# pca63557_sheet3_motor.net
KiCad netlist of a schematic drawn in Altium Designer
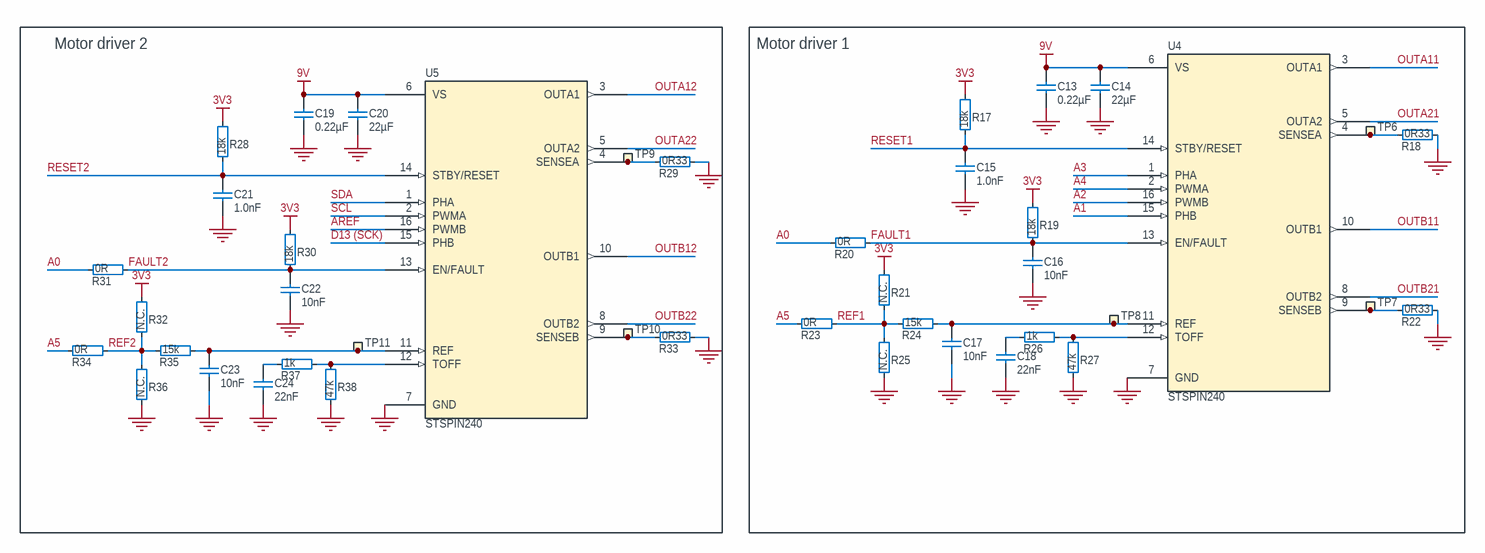
[diagram p0: pca63557_sheet3_motor.SchDoc]

(export (version "E")
  (design (tool "Eeschema 10.0.6"))
  (components
    (comp (ref "C13")
      (value "0.22µF")
      (footprint "CAPC1005X04L")
      (description "Capacitor, X7R, ±0.10%, 16V")
      (fields
        (field (name "PART NUMBER") "C0402-0.22µ-16V-X7R-CL05B224KO5NNNC")
        (field (name "MANUFACTURER") "Samsung Electro-Mechanics")
        (field (name "AUTHOR") "mam1")
      )
      (libsource (lib "AltiumLib") (part "CAP"))
    )
    (comp (ref "C14")
      (value "22µF")
      (footprint "CAPC1608X06L")
      (description "Capacitor, X5R, ±0.20%, 16V")
      (fields
        (field (name "PART NUMBER") "C0603-22µ-16V-X5R-CL10A226MO7JZNC")
        (field (name "MANUFACTURER") "Samsung Electro-Mechanics")
        (field (name "AUTHOR") "mam1")
      )
      (libsource (lib "AltiumLib") (part "CAP"))
    )
    (comp (ref "C15")
      (value "1.0nF")
      (footprint "CAPC1005X04L")
      (description "Capacitor, X7R, ±10%")
      (fields
        (field (name "PART NUMBER") "C0402-1n0")
        (field (name "MANUFACTURER") "N.A.")
        (field (name "AUTHOR") "rsk")
      )
      (libsource (lib "AltiumLib") (part "CAP"))
    )
    (comp (ref "C16")
      (value "10nF")
      (footprint "CAPC1005X04L")
      (description "Capacitor, X7R, ±10%")
      (fields
        (field (name "PART NUMBER") "C0402-10n")
        (field (name "MANUFACTURER") "N.A.")
        (field (name "AUTHOR") "rsk")
      )
      (libsource (lib "AltiumLib") (part "CAP"))
    )
    (comp (ref "C17")
      (value "10nF")
      (footprint "CAPC1005X04L")
      (description "Capacitor, X7R, ±10%")
      (fields
        (field (name "PART NUMBER") "C0402-10n")
        (field (name "MANUFACTURER") "N.A.")
        (field (name "AUTHOR") "rsk")
      )
      (libsource (lib "AltiumLib") (part "CAP"))
    )
    (comp (ref "C18")
      (value "22nF")
      (footprint "CAPC1005X04L")
      (description "Capacitor, X7R, ±10%")
      (fields
        (field (name "PART NUMBER") "C0402-22n")
        (field (name "MANUFACTURER") "N.A.")
        (field (name "AUTHOR") "rsk")
      )
      (libsource (lib "AltiumLib") (part "CAP"))
    )
    (comp (ref "C19")
      (value "0.22µF")
      (footprint "CAPC1005X04L")
      (description "Capacitor, X7R, ±0.10%, 16V")
      (fields
        (field (name "PART NUMBER") "C0402-0.22µ-16V-X7R-CL05B224KO5NNNC")
        (field (name "MANUFACTURER") "Samsung Electro-Mechanics")
        (field (name "AUTHOR") "mam1")
      )
      (libsource (lib "AltiumLib") (part "CAP"))
    )
    (comp (ref "C20")
      (value "22µF")
      (footprint "CAPC1608X06L")
      (description "Capacitor, X5R, ±0.20%, 16V")
      (fields
        (field (name "PART NUMBER") "C0603-22µ-16V-X5R-CL10A226MO7JZNC")
        (field (name "MANUFACTURER") "Samsung Electro-Mechanics")
        (field (name "AUTHOR") "mam1")
      )
      (libsource (lib "AltiumLib") (part "CAP"))
    )
    (comp (ref "C21")
      (value "1.0nF")
      (footprint "CAPC1005X04L")
      (description "Capacitor, X7R, ±10%")
      (fields
        (field (name "PART NUMBER") "C0402-1n0")
        (field (name "MANUFACTURER") "N.A.")
        (field (name "AUTHOR") "rsk")
      )
      (libsource (lib "AltiumLib") (part "CAP"))
    )
    (comp (ref "C22")
      (value "10nF")
      (footprint "CAPC1005X04L")
      (description "Capacitor, X7R, ±10%")
      (fields
        (field (name "PART NUMBER") "C0402-10n")
        (field (name "MANUFACTURER") "N.A.")
        (field (name "AUTHOR") "rsk")
      )
      (libsource (lib "AltiumLib") (part "CAP"))
    )
    (comp (ref "C23")
      (value "10nF")
      (footprint "CAPC1005X04L")
      (description "Capacitor, X7R, ±10%")
      (fields
        (field (name "PART NUMBER") "C0402-10n")
        (field (name "MANUFACTURER") "N.A.")
        (field (name "AUTHOR") "rsk")
      )
      (libsource (lib "AltiumLib") (part "CAP"))
    )
    (comp (ref "C24")
      (value "22nF")
      (footprint "CAPC1005X04L")
      (description "Capacitor, X7R, ±10%")
      (fields
        (field (name "PART NUMBER") "C0402-22n")
        (field (name "MANUFACTURER") "N.A.")
        (field (name "AUTHOR") "rsk")
      )
      (libsource (lib "AltiumLib") (part "CAP"))
    )
    (comp (ref "R17")
      (value "18k")
      (footprint "RESC1005X04L")
      (description "Resistor, ±1%, 0.063W")
      (fields
        (field (name "PART NUMBER") "R0402-18k")
        (field (name "MANUFACTURER") "N.A.")
        (field (name "AUTHOR") "rsk")
      )
      (libsource (lib "AltiumLib") (part "RES"))
    )
    (comp (ref "R18")
      (value "0R33")
      (footprint "RESC3216X08N")
      (description "330 Ohms ±0.5% 1W Chip Resistor 1206 (3216 Metric)")
      (fields
        (field (name "PART NUMBER") "R1206-0R33-0.5%-1W-HRG3216P-3300-D-T1")
        (field (name "MANUFACTURER") "Susumu")
        (field (name "AUTHOR") "mam1")
      )
      (libsource (lib "AltiumLib") (part "RES"))
    )
    (comp (ref "R19")
      (value "18k")
      (footprint "RESC1005X04L")
      (description "Resistor, ±1%, 0.063W")
      (fields
        (field (name "PART NUMBER") "R0402-18k")
        (field (name "MANUFACTURER") "N.A.")
        (field (name "AUTHOR") "rsk")
      )
      (libsource (lib "AltiumLib") (part "RES"))
    )
    (comp (ref "R20")
      (value "0R")
      (footprint "RESC1005X04L")
      (description "Resistor, ±5%, 0.063W")
      (fields
        (field (name "PART NUMBER") "R0402-0R")
        (field (name "MANUFACTURER") "N.A.")
        (field (name "AUTHOR") "rsk")
      )
      (libsource (lib "AltiumLib") (part "RES"))
    )
    (comp (ref "R21")
      (value "N.C.")
      (footprint "RESC1005X04L_NC")
      (description "Not mounted")
      (fields
        (field (name "PART NUMBER") "R0402-N.C.")
        (field (name "MANUFACTURER") "N.A.")
        (field (name "AUTHOR") "rsk")
      )
      (libsource (lib "AltiumLib") (part "RES"))
    )
    (comp (ref "R22")
      (value "0R33")
      (footprint "RESC3216X08N")
      (description "330 Ohms ±0.5% 1W Chip Resistor 1206 (3216 Metric)")
      (fields
        (field (name "PART NUMBER") "R1206-0R33-0.5%-1W-HRG3216P-3300-D-T1")
        (field (name "MANUFACTURER") "Susumu")
        (field (name "AUTHOR") "mam1")
      )
      (libsource (lib "AltiumLib") (part "RES"))
    )
    (comp (ref "R23")
      (value "0R")
      (footprint "RESC1005X04L")
      (description "Resistor, ±5%, 0.063W")
      (fields
        (field (name "PART NUMBER") "R0402-0R")
        (field (name "MANUFACTURER") "N.A.")
        (field (name "AUTHOR") "rsk")
      )
      (libsource (lib "AltiumLib") (part "RES"))
    )
    (comp (ref "R24")
      (value "15k")
      (footprint "RESC1005X04L")
      (description "Resistor, ±1%, 0.063W")
      (fields
        (field (name "PART NUMBER") "R0402-15k")
        (field (name "MANUFACTURER") "N.A.")
        (field (name "AUTHOR") "rsk")
      )
      (libsource (lib "AltiumLib") (part "RES"))
    )
    (comp (ref "R25")
      (value "N.C.")
      (footprint "RESC1005X04L_NC")
      (description "Not mounted")
      (fields
        (field (name "PART NUMBER") "R0402-N.C.")
        (field (name "MANUFACTURER") "N.A.")
        (field (name "AUTHOR") "rsk")
      )
      (libsource (lib "AltiumLib") (part "RES"))
    )
    (comp (ref "R26")
      (value "1k")
      (footprint "RESC1005X04L")
      (description "Resistor, ±1%, 0.063W")
      (fields
        (field (name "PART NUMBER") "R0402-1k0")
        (field (name "MANUFACTURER") "N.A.")
        (field (name "AUTHOR") "rsk")
      )
      (libsource (lib "AltiumLib") (part "RES"))
    )
    (comp (ref "R27")
      (value "47k")
      (footprint "RESC1005X04L")
      (description "Resistor, ±1%, 0.063W")
      (fields
        (field (name "PART NUMBER") "R0402-47k")
        (field (name "MANUFACTURER") "N.A.")
        (field (name "AUTHOR") "rsk")
      )
      (libsource (lib "AltiumLib") (part "RES"))
    )
    (comp (ref "R28")
      (value "18k")
      (footprint "RESC1005X04L")
      (description "Resistor, ±1%, 0.063W")
      (fields
        (field (name "PART NUMBER") "R0402-18k")
        (field (name "MANUFACTURER") "N.A.")
        (field (name "AUTHOR") "rsk")
      )
      (libsource (lib "AltiumLib") (part "RES"))
    )
    (comp (ref "R29")
      (value "0R33")
      (footprint "RESC3216X08N")
      (description "330 Ohms ±0.5% 1W Chip Resistor 1206 (3216 Metric)")
      (fields
        (field (name "PART NUMBER") "R1206-0R33-0.5%-1W-HRG3216P-3300-D-T1")
        (field (name "MANUFACTURER") "Susumu")
        (field (name "AUTHOR") "mam1")
      )
      (libsource (lib "AltiumLib") (part "RES"))
    )
    (comp (ref "R30")
      (value "18k")
      (footprint "RESC1005X04L")
      (description "Resistor, ±1%, 0.063W")
      (fields
        (field (name "PART NUMBER") "R0402-18k")
        (field (name "MANUFACTURER") "N.A.")
        (field (name "AUTHOR") "rsk")
      )
      (libsource (lib "AltiumLib") (part "RES"))
    )
    (comp (ref "R31")
      (value "0R")
      (footprint "RESC1005X04L")
      (description "Resistor, ±5%, 0.063W")
      (fields
        (field (name "PART NUMBER") "R0402-0R")
        (field (name "MANUFACTURER") "N.A.")
        (field (name "AUTHOR") "rsk")
      )
      (libsource (lib "AltiumLib") (part "RES"))
    )
    (comp (ref "R32")
      (value "N.C.")
      (footprint "RESC1005X04L_NC")
      (description "Not mounted")
      (fields
        (field (name "PART NUMBER") "R0402-N.C.")
        (field (name "MANUFACTURER") "N.A.")
        (field (name "AUTHOR") "rsk")
      )
      (libsource (lib "AltiumLib") (part "RES"))
    )
    (comp (ref "R33")
      (value "0R33")
      (footprint "RESC3216X08N")
      (description "330 Ohms ±0.5% 1W Chip Resistor 1206 (3216 Metric)")
      (fields
        (field (name "PART NUMBER") "R1206-0R33-0.5%-1W-HRG3216P-3300-D-T1")
        (field (name "MANUFACTURER") "Susumu")
        (field (name "AUTHOR") "mam1")
      )
      (libsource (lib "AltiumLib") (part "RES"))
    )
    (comp (ref "R34")
      (value "0R")
      (footprint "RESC1005X04L")
      (description "Resistor, ±5%, 0.063W")
      (fields
        (field (name "PART NUMBER") "R0402-0R")
        (field (name "MANUFACTURER") "N.A.")
        (field (name "AUTHOR") "rsk")
      )
      (libsource (lib "AltiumLib") (part "RES"))
    )
    (comp (ref "R35")
      (value "15k")
      (footprint "RESC1005X04L")
      (description "Resistor, ±1%, 0.063W")
      (fields
        (field (name "PART NUMBER") "R0402-15k")
        (field (name "MANUFACTURER") "N.A.")
        (field (name "AUTHOR") "rsk")
      )
      (libsource (lib "AltiumLib") (part "RES"))
    )
    (comp (ref "R36")
      (value "N.C.")
      (footprint "RESC1005X04L_NC")
      (description "Not mounted")
      (fields
        (field (name "PART NUMBER") "R0402-N.C.")
        (field (name "MANUFACTURER") "N.A.")
        (field (name "AUTHOR") "rsk")
      )
      (libsource (lib "AltiumLib") (part "RES"))
    )
    (comp (ref "R37")
      (value "1k")
      (footprint "RESC1005X04L")
      (description "Resistor, ±1%, 0.063W")
      (fields
        (field (name "PART NUMBER") "R0402-1k0")
        (field (name "MANUFACTURER") "N.A.")
        (field (name "AUTHOR") "rsk")
      )
      (libsource (lib "AltiumLib") (part "RES"))
    )
    (comp (ref "R38")
      (value "47k")
      (footprint "RESC1005X04L")
      (description "Resistor, ±1%, 0.063W")
      (fields
        (field (name "PART NUMBER") "R0402-47k")
        (field (name "MANUFACTURER") "N.A.")
        (field (name "AUTHOR") "rsk")
      )
      (libsource (lib "AltiumLib") (part "RES"))
    )
    (comp (ref "TP6")
      (value "Ø1.5mm,SMD")
      (footprint "TP_SMD_D1.5mm")
      (description "1.5mm circular SMD testpad")
      (fields
        (field (name "PART NUMBER") "TP_SMD_Ø1.5MM")
        (field (name "MANUFACTURER") "Nordic Semiconductor")
        (field (name "AUTHOR") "rsk")
      )
      (libsource (lib "AltiumLib") (part "TESTPAD"))
    )
    (comp (ref "TP7")
      (value "Ø1.5mm,SMD")
      (footprint "TP_SMD_D1.5mm")
      (description "1.5mm circular SMD testpad")
      (fields
        (field (name "PART NUMBER") "TP_SMD_Ø1.5MM")
        (field (name "MANUFACTURER") "Nordic Semiconductor")
        (field (name "AUTHOR") "rsk")
      )
      (libsource (lib "AltiumLib") (part "TESTPAD"))
    )
    (comp (ref "TP8")
      (value "Ø1.5mm,SMD")
      (footprint "TP_SMD_D1.5mm")
      (description "1.5mm circular SMD testpad")
      (fields
        (field (name "PART NUMBER") "TP_SMD_Ø1.5MM")
        (field (name "MANUFACTURER") "Nordic Semiconductor")
        (field (name "AUTHOR") "rsk")
      )
      (libsource (lib "AltiumLib") (part "TESTPAD"))
    )
    (comp (ref "TP9")
      (value "Ø1.5mm,SMD")
      (footprint "TP_SMD_D1.5mm")
      (description "1.5mm circular SMD testpad")
      (fields
        (field (name "PART NUMBER") "TP_SMD_Ø1.5MM")
        (field (name "MANUFACTURER") "Nordic Semiconductor")
        (field (name "AUTHOR") "rsk")
      )
      (libsource (lib "AltiumLib") (part "TESTPAD"))
    )
    (comp (ref "TP10")
      (value "Ø1.5mm,SMD")
      (footprint "TP_SMD_D1.5mm")
      (description "1.5mm circular SMD testpad")
      (fields
        (field (name "PART NUMBER") "TP_SMD_Ø1.5MM")
        (field (name "MANUFACTURER") "Nordic Semiconductor")
        (field (name "AUTHOR") "rsk")
      )
      (libsource (lib "AltiumLib") (part "TESTPAD"))
    )
    (comp (ref "TP11")
      (value "Ø1.5mm,SMD")
      (footprint "TP_SMD_D1.5mm")
      (description "1.5mm circular SMD testpad")
      (fields
        (field (name "PART NUMBER") "TP_SMD_Ø1.5MM")
        (field (name "MANUFACTURER") "Nordic Semiconductor")
        (field (name "AUTHOR") "rsk")
      )
      (libsource (lib "AltiumLib") (part "TESTPAD"))
    )
    (comp (ref "U4")
      (value "STSPIN240")
      (footprint "STSPIN240")
      (description "LOW VOLTAGE DUAL BRUSH DC MOTOR")
      (fields (field (name "MANUFACTURER") "STMicroelectronics") (field (name "AUTHOR") "mam1"))
      (libsource (lib "AltiumLib") (part "STSPIN240"))
    )
    (comp (ref "U5")
      (value "STSPIN240")
      (footprint "STSPIN240")
      (description "LOW VOLTAGE DUAL BRUSH DC MOTOR")
      (fields (field (name "MANUFACTURER") "STMicroelectronics") (field (name "AUTHOR") "mam1"))
      (libsource (lib "AltiumLib") (part "STSPIN240"))
    )
  )
  (nets
    (net (code "1") (name "/A0") (class "Default")
      (node (ref "R20") (pin "1") (pinfunction "1_1") (pintype "passive"))
      (node (ref "R31") (pin "1") (pinfunction "1_1") (pintype "passive"))
    )
    (net (code "2") (name "/A1") (class "Default")
      (node (ref "U4") (pin "15") (pinfunction "PHB_15") (pintype "input"))
    )
    (net (code "3") (name "/A2") (class "Default")
      (node (ref "U4") (pin "16") (pinfunction "PWMB_16") (pintype "input"))
    )
    (net (code "4") (name "/A3") (class "Default")
      (node (ref "U4") (pin "1") (pinfunction "PHA_1") (pintype "input"))
    )
    (net (code "5") (name "/A4") (class "Default")
      (node (ref "U4") (pin "2") (pinfunction "PWMA_2") (pintype "input"))
    )
    (net (code "6") (name "/A5") (class "Default")
      (node (ref "R23") (pin "1") (pinfunction "1_1") (pintype "passive"))
      (node (ref "R34") (pin "1") (pinfunction "1_1") (pintype "passive"))
    )
    (net (code "7") (name "/AREF") (class "Default")
      (node (ref "U5") (pin "16") (pinfunction "PWMB_16") (pintype "input"))
    )
    (net (code "8") (name "/D13 (SCK)") (class "Default")
      (node (ref "U5") (pin "15") (pinfunction "PHB_15") (pintype "input"))
    )
    (net (code "9") (name "/FAULT1") (class "Default")
      (node (ref "C16") (pin "2") (pinfunction "2_2") (pintype "passive"))
      (node (ref "R19") (pin "1") (pinfunction "1_1") (pintype "passive"))
      (node (ref "R20") (pin "2") (pinfunction "2_2") (pintype "passive"))
      (node (ref "U4") (pin "13") (pinfunction "EN/FAULT_13") (pintype "input"))
    )
    (net (code "10") (name "/FAULT2") (class "Default")
      (node (ref "C22") (pin "2") (pinfunction "2_2") (pintype "passive"))
      (node (ref "R30") (pin "1") (pinfunction "1_1") (pintype "passive"))
      (node (ref "R31") (pin "2") (pinfunction "2_2") (pintype "passive"))
      (node (ref "U5") (pin "13") (pinfunction "EN/FAULT_13") (pintype "input"))
    )
    (net (code "11") (name "/OUTA11") (class "Default")
      (node (ref "U4") (pin "3") (pinfunction "OUTA1_3") (pintype "output"))
    )
    (net (code "12") (name "/OUTA12") (class "Default")
      (node (ref "U5") (pin "3") (pinfunction "OUTA1_3") (pintype "output"))
    )
    (net (code "13") (name "/OUTA21") (class "Default")
      (node (ref "U4") (pin "5") (pinfunction "OUTA2_5") (pintype "output"))
    )
    (net (code "14") (name "/OUTA22") (class "Default")
      (node (ref "U5") (pin "5") (pinfunction "OUTA2_5") (pintype "output"))
    )
    (net (code "15") (name "/OUTB11") (class "Default")
      (node (ref "U4") (pin "10") (pinfunction "OUTB1_10") (pintype "output"))
    )
    (net (code "16") (name "/OUTB12") (class "Default")
      (node (ref "U5") (pin "10") (pinfunction "OUTB1_10") (pintype "output"))
    )
    (net (code "17") (name "/OUTB21") (class "Default")
      (node (ref "U4") (pin "8") (pinfunction "OUTB2_8") (pintype "output"))
    )
    (net (code "18") (name "/OUTB22") (class "Default")
      (node (ref "U5") (pin "8") (pinfunction "OUTB2_8") (pintype "output"))
    )
    (net (code "19") (name "/REF1") (class "Default")
      (node (ref "R21") (pin "1") (pinfunction "1_1") (pintype "passive"))
      (node (ref "R23") (pin "2") (pinfunction "2_2") (pintype "passive"))
      (node (ref "R24") (pin "1") (pinfunction "1_1") (pintype "passive"))
      (node (ref "R25") (pin "2") (pinfunction "2_2") (pintype "passive"))
    )
    (net (code "20") (name "/REF2") (class "Default")
      (node (ref "R32") (pin "1") (pinfunction "1_1") (pintype "passive"))
      (node (ref "R34") (pin "2") (pinfunction "2_2") (pintype "passive"))
      (node (ref "R35") (pin "1") (pinfunction "1_1") (pintype "passive"))
      (node (ref "R36") (pin "2") (pinfunction "2_2") (pintype "passive"))
    )
    (net (code "21") (name "/RESET1") (class "Default")
      (node (ref "C15") (pin "2") (pinfunction "2_2") (pintype "passive"))
      (node (ref "R17") (pin "1") (pinfunction "1_1") (pintype "passive"))
      (node (ref "U4") (pin "14") (pinfunction "STBY/RESET_14") (pintype "input"))
    )
    (net (code "22") (name "/RESET2") (class "Default")
      (node (ref "C21") (pin "2") (pinfunction "2_2") (pintype "passive"))
      (node (ref "R28") (pin "1") (pinfunction "1_1") (pintype "passive"))
      (node (ref "U5") (pin "14") (pinfunction "STBY/RESET_14") (pintype "input"))
    )
    (net (code "23") (name "/SCL") (class "Default")
      (node (ref "U5") (pin "2") (pinfunction "PWMA_2") (pintype "input"))
    )
    (net (code "24") (name "/SDA") (class "Default")
      (node (ref "U5") (pin "1") (pinfunction "PHA_1") (pintype "input"))
    )
    (net (code "25") (name "3V3") (class "Default")
      (node (ref "R17") (pin "2") (pinfunction "2_2") (pintype "passive"))
      (node (ref "R19") (pin "2") (pinfunction "2_2") (pintype "passive"))
      (node (ref "R21") (pin "2") (pinfunction "2_2") (pintype "passive"))
      (node (ref "R28") (pin "2") (pinfunction "2_2") (pintype "passive"))
      (node (ref "R30") (pin "2") (pinfunction "2_2") (pintype "passive"))
      (node (ref "R32") (pin "2") (pinfunction "2_2") (pintype "passive"))
    )
    (net (code "26") (name "9V") (class "Default")
      (node (ref "C13") (pin "2") (pinfunction "2_2") (pintype "passive"))
      (node (ref "C14") (pin "2") (pinfunction "2_2") (pintype "passive"))
      (node (ref "C19") (pin "2") (pinfunction "2_2") (pintype "passive"))
      (node (ref "C20") (pin "2") (pinfunction "2_2") (pintype "passive"))
      (node (ref "U4") (pin "6") (pinfunction "VS_6") (pintype "power_in"))
      (node (ref "U5") (pin "6") (pinfunction "VS_6") (pintype "power_in"))
    )
    (net (code "27") (name "GND") (class "Default")
      (node (ref "C13") (pin "1") (pinfunction "1_1") (pintype "passive"))
      (node (ref "C14") (pin "1") (pinfunction "1_1") (pintype "passive"))
      (node (ref "C15") (pin "1") (pinfunction "1_1") (pintype "passive"))
      (node (ref "C16") (pin "1") (pinfunction "1_1") (pintype "passive"))
      (node (ref "C17") (pin "1") (pinfunction "1_1") (pintype "passive"))
      (node (ref "C18") (pin "1") (pinfunction "1_1") (pintype "passive"))
      (node (ref "C19") (pin "1") (pinfunction "1_1") (pintype "passive"))
      (node (ref "C20") (pin "1") (pinfunction "1_1") (pintype "passive"))
      (node (ref "C21") (pin "1") (pinfunction "1_1") (pintype "passive"))
      (node (ref "C22") (pin "1") (pinfunction "1_1") (pintype "passive"))
      (node (ref "C23") (pin "1") (pinfunction "1_1") (pintype "passive"))
      (node (ref "C24") (pin "1") (pinfunction "1_1") (pintype "passive"))
      (node (ref "R18") (pin "2") (pinfunction "2_2") (pintype "passive"))
      (node (ref "R22") (pin "2") (pinfunction "2_2") (pintype "passive"))
      (node (ref "R25") (pin "1") (pinfunction "1_1") (pintype "passive"))
      (node (ref "R27") (pin "1") (pinfunction "1_1") (pintype "passive"))
      (node (ref "R29") (pin "2") (pinfunction "2_2") (pintype "passive"))
      (node (ref "R33") (pin "2") (pinfunction "2_2") (pintype "passive"))
      (node (ref "R36") (pin "1") (pinfunction "1_1") (pintype "passive"))
      (node (ref "R38") (pin "1") (pinfunction "1_1") (pintype "passive"))
      (node (ref "U4") (pin "7") (pinfunction "GND_7") (pintype "power_in"))
      (node (ref "U5") (pin "7") (pinfunction "GND_7") (pintype "power_in"))
    )
    (net (code "28") (name "Net-(C18-Pad2)") (class "Default")
      (node (ref "C18") (pin "2") (pinfunction "2_2") (pintype "passive"))
      (node (ref "R26") (pin "1") (pinfunction "1_1") (pintype "passive"))
    )
    (net (code "29") (name "Net-(C24-Pad2)") (class "Default")
      (node (ref "C24") (pin "2") (pinfunction "2_2") (pintype "passive"))
      (node (ref "R37") (pin "1") (pinfunction "1_1") (pintype "passive"))
    )
    (net (code "30") (name "Net-(U4-REF)") (class "Default")
      (node (ref "C17") (pin "2") (pinfunction "2_2") (pintype "passive"))
      (node (ref "R24") (pin "2") (pinfunction "2_2") (pintype "passive"))
      (node (ref "TP8") (pin "1") (pinfunction "1_1") (pintype "passive"))
      (node (ref "U4") (pin "11") (pinfunction "REF_11") (pintype "input"))
    )
    (net (code "31") (name "Net-(U4-SENSEA)") (class "Default")
      (node (ref "R18") (pin "1") (pinfunction "1_1") (pintype "passive"))
      (node (ref "TP6") (pin "1") (pinfunction "1_1") (pintype "passive"))
      (node (ref "U4") (pin "4") (pinfunction "SENSEA_4") (pintype "output"))
    )
    (net (code "32") (name "Net-(U4-SENSEB)") (class "Default")
      (node (ref "R22") (pin "1") (pinfunction "1_1") (pintype "passive"))
      (node (ref "TP7") (pin "1") (pinfunction "1_1") (pintype "passive"))
      (node (ref "U4") (pin "9") (pinfunction "SENSEB_9") (pintype "output"))
    )
    (net (code "33") (name "Net-(U4-TOFF)") (class "Default")
      (node (ref "R26") (pin "2") (pinfunction "2_2") (pintype "passive"))
      (node (ref "R27") (pin "2") (pinfunction "2_2") (pintype "passive"))
      (node (ref "U4") (pin "12") (pinfunction "TOFF_12") (pintype "input"))
    )
    (net (code "34") (name "Net-(U5-REF)") (class "Default")
      (node (ref "C23") (pin "2") (pinfunction "2_2") (pintype "passive"))
      (node (ref "R35") (pin "2") (pinfunction "2_2") (pintype "passive"))
      (node (ref "TP11") (pin "1") (pinfunction "1_1") (pintype "passive"))
      (node (ref "U5") (pin "11") (pinfunction "REF_11") (pintype "input"))
    )
    (net (code "35") (name "Net-(U5-SENSEA)") (class "Default")
      (node (ref "R29") (pin "1") (pinfunction "1_1") (pintype "passive"))
      (node (ref "TP9") (pin "1") (pinfunction "1_1") (pintype "passive"))
      (node (ref "U5") (pin "4") (pinfunction "SENSEA_4") (pintype "output"))
    )
    (net (code "36") (name "Net-(U5-SENSEB)") (class "Default")
      (node (ref "R33") (pin "1") (pinfunction "1_1") (pintype "passive"))
      (node (ref "TP10") (pin "1") (pinfunction "1_1") (pintype "passive"))
      (node (ref "U5") (pin "9") (pinfunction "SENSEB_9") (pintype "output"))
    )
    (net (code "37") (name "Net-(U5-TOFF)") (class "Default")
      (node (ref "R37") (pin "2") (pinfunction "2_2") (pintype "passive"))
      (node (ref "R38") (pin "2") (pinfunction "2_2") (pintype "passive"))
      (node (ref "U5") (pin "12") (pinfunction "TOFF_12") (pintype "input"))
    )
  )
)
